# RoboKit.net
KiCad netlist of a schematic drawn in EAGLE
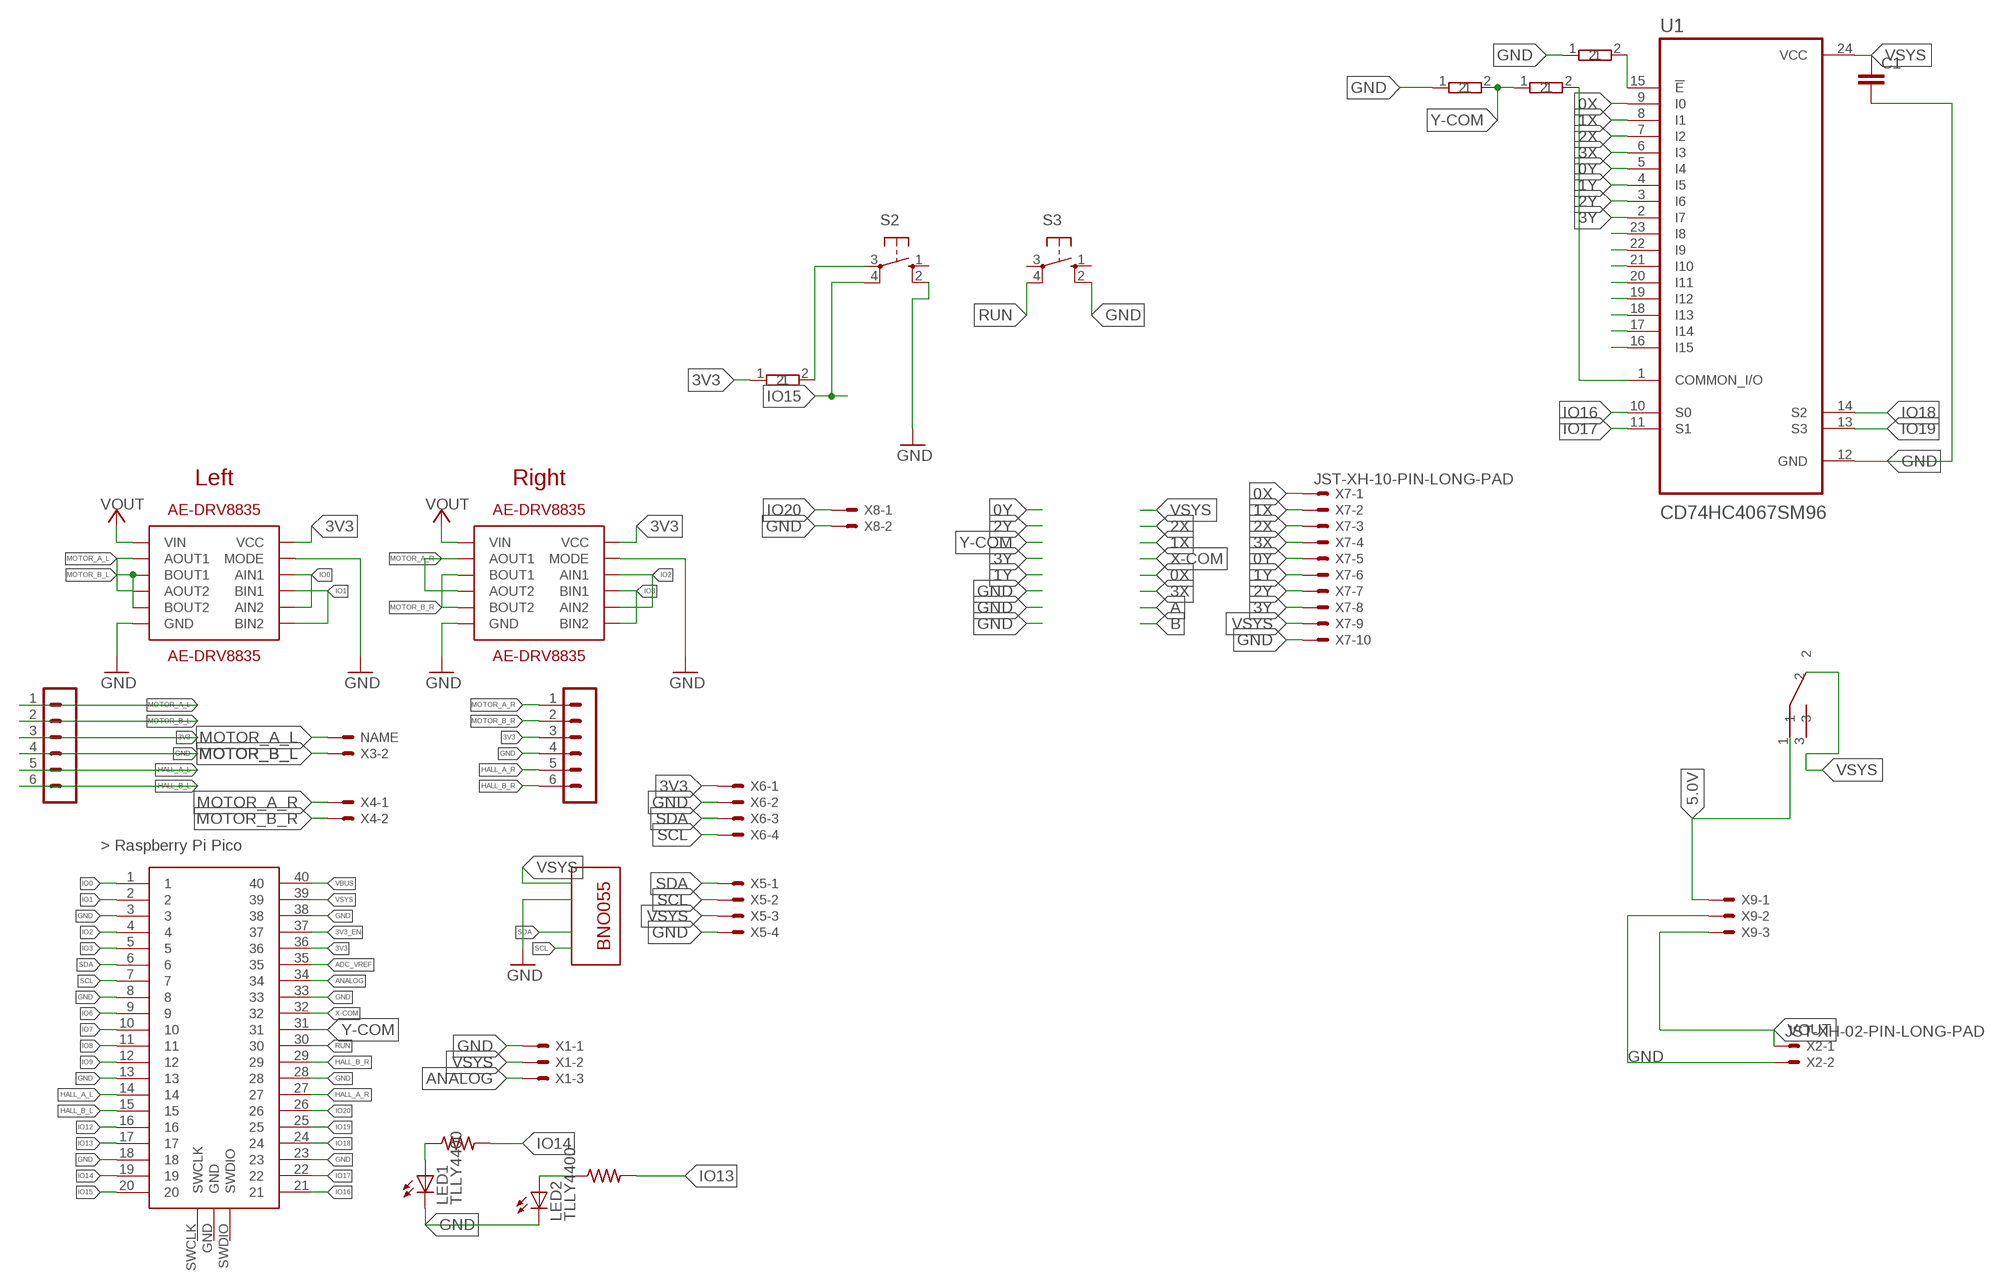
[diagram p0: schematic, sheet 1]

(export (version "E")
  (design (tool "Eeschema 10.0.6"))
  (components
    (comp (ref "C1")
      (value "C-EU025-024X044")
      (footprint "eagle-import:C025-024X044")
      (libsource (lib "eagle-import") (part "C-EU025-024X044"))
    )
    (comp (ref "CONNECTOR1")
      (value "RESISTER")
      (footprint "eagle-import:RESISTER_SOCKET")
      (libsource (lib "eagle-import") (part "RESISTER"))
    )
    (comp (ref "CONNECTOR4")
      (value "RESISTER")
      (footprint "eagle-import:RESISTER_SOCKET")
      (libsource (lib "eagle-import") (part "RESISTER"))
    )
    (comp (ref "CONNECTOR5")
      (value "RESISTER")
      (footprint "eagle-import:RESISTER_SOCKET")
      (libsource (lib "eagle-import") (part "RESISTER"))
    )
    (comp (ref "CONNECTOR6")
      (value "RESISTER")
      (footprint "eagle-import:RESISTER_SOCKET")
      (libsource (lib "eagle-import") (part "RESISTER"))
    )
    (comp (ref "LED1")
      (value "TLLY4400")
      (footprint "eagle-import:LED3MM")
      (fields (field (name "MF") "VISHAY SEMICONDUCTOR"))
      (libsource (lib "eagle-import") (part "TLLY4400"))
    )
    (comp (ref "LED2")
      (value "TLLY4400")
      (footprint "eagle-import:LED3MM")
      (fields (field (name "MF") "VISHAY SEMICONDUCTOR"))
      (libsource (lib "eagle-import") (part "TLLY4400"))
    )
    (comp (ref "P1")
      (value "B6B-PH-K")
      (footprint "eagle-import:B6B-PH-K")
      (libsource (lib "eagle-import") (part "B6B-PH-K"))
    )
    (comp (ref "P2")
      (value "B6B-PH-K")
      (footprint "eagle-import:B6B-PH-K")
      (libsource (lib "eagle-import") (part "B6B-PH-K"))
    )
    (comp (ref "R2")
      (value "R-US_R0603")
      (footprint "eagle-import:R0603")
      (libsource (lib "eagle-import") (part "R-US_R0603"))
    )
    (comp (ref "R3")
      (value "R-US_R0603")
      (footprint "eagle-import:R0603")
      (libsource (lib "eagle-import") (part "R-US_R0603"))
    )
    (comp (ref "S2")
      (value "40-XX")
      (footprint "eagle-import:B3F-40XX")
      (fields (field (name "MF") "OMRON COMPONENTS USA") (field (name "MPN") "B3F-4000"))
      (libsource (lib "eagle-import") (part "40-XX"))
    )
    (comp (ref "S3")
      (value "10-XX")
      (footprint "eagle-import:B3F-10XX")
      (fields (field (name "MPN") "B3F-1000"))
      (libsource (lib "eagle-import") (part "10-XX"))
    )
    (comp (ref "U$1")
      (value "RASPBERRY-PI-PICO_TH")
      (footprint "eagle-import:FT_RASPBERRY-PI-PICO_TH")
      (libsource (lib "eagle-import") (part "RASPBERRY-PI-PICO_TH"))
    )
    (comp (ref "U$2")
      (value "AE-DRV8835")
      (footprint "eagle-import:AE-DRV8835")
      (libsource (lib "eagle-import") (part "AE-DRV8835"))
    )
    (comp (ref "U$3")
      (value "AE-DRV8835")
      (footprint "eagle-import:AE-DRV8835")
      (libsource (lib "eagle-import") (part "AE-DRV8835"))
    )
    (comp (ref "U$4")
      (value "AE-BNO055-BO")
      (footprint "eagle-import:AE-BNO055-BO")
      (libsource (lib "eagle-import") (part "AE-BNO055-BO"))
    )
    (comp (ref "U$8") (value "SW") (footprint "eagle-import:SW") (libsource (lib "eagle-import") (part "SW")))
    (comp (ref "U1")
      (value "CD74HC4067SM96")
      (footprint "eagle-import:SOP65P780X200-24N")
      (fields (field (name "MF") "Texas Instruments"))
      (libsource (lib "eagle-import") (part "CD74HC4067SM96"))
    )
    (comp (ref "X1")
      (value "JST-XH-03-PIN-LONG-PAD")
      (footprint "eagle-import:JST-XH-03-PACKAGE-LONG-PAD")
      (libsource (lib "eagle-import") (part "JST-XH-03-PIN-LONG-PAD"))
    )
    (comp (ref "X2")
      (value "JST-XH-02-PIN-LONG-PAD")
      (footprint "eagle-import:JST-XH-02-PACKAGE-LONG-PAD")
      (libsource (lib "eagle-import") (part "JST-XH-02-PIN-LONG-PAD"))
    )
    (comp (ref "X3")
      (value "JST-XH-02-PIN-LONG-PAD")
      (footprint "eagle-import:JST-XH-02-PACKAGE-LONG-PAD")
      (libsource (lib "eagle-import") (part "JST-XH-02-PIN-LONG-PAD"))
    )
    (comp (ref "X4")
      (value "JST-XH-02-PIN-LONG-PAD")
      (footprint "eagle-import:JST-XH-02-PACKAGE-LONG-PAD")
      (libsource (lib "eagle-import") (part "JST-XH-02-PIN-LONG-PAD"))
    )
    (comp (ref "X5")
      (value "JST-XH-04-PIN-LONG-PAD")
      (footprint "eagle-import:JST-XH-04-PACKAGE-LONG-PAD")
      (libsource (lib "eagle-import") (part "JST-XH-04-PIN-LONG-PAD"))
    )
    (comp (ref "X6")
      (value "JST-XH-04-PIN-LONG-PAD")
      (footprint "eagle-import:JST-XH-04-PACKAGE-LONG-PAD")
      (libsource (lib "eagle-import") (part "JST-XH-04-PIN-LONG-PAD"))
    )
    (comp (ref "X7")
      (value "JST-XH-10-PIN-LONG-PAD")
      (footprint "eagle-import:JST-XH-10-PACKAGE-LONG-PAD")
      (libsource (lib "eagle-import") (part "JST-XH-10-PIN-LONG-PAD"))
    )
    (comp (ref "X8")
      (value "JST-XH-02-PIN-LONG-PAD")
      (footprint "eagle-import:JST-XH-02-PACKAGE-LONG-PAD")
      (libsource (lib "eagle-import") (part "JST-XH-02-PIN-LONG-PAD"))
    )
    (comp (ref "X9")
      (value "JST-XH-03-PIN-LONG-PAD")
      (footprint "eagle-import:JST-XH-03-PACKAGE-LONG-PAD")
      (libsource (lib "eagle-import") (part "JST-XH-03-PIN-LONG-PAD"))
    )
  )
  (nets
    (net (code "1") (name "0X") (class "Default")
      (node (ref "U1") (pin "9") (pinfunction "I0_9") (pintype "input"))
      (node (ref "X7") (pin "1") (pinfunction "S_1") (pintype "passive"))
    )
    (net (code "2") (name "0Y") (class "Default")
      (node (ref "U1") (pin "5") (pinfunction "I4_5") (pintype "input"))
      (node (ref "X7") (pin "5") (pinfunction "S_5") (pintype "passive"))
    )
    (net (code "3") (name "1X") (class "Default")
      (node (ref "U1") (pin "8") (pinfunction "I1_8") (pintype "input"))
      (node (ref "X7") (pin "2") (pinfunction "S_2") (pintype "passive"))
    )
    (net (code "4") (name "1Y") (class "Default")
      (node (ref "U1") (pin "4") (pinfunction "I5_4") (pintype "input"))
      (node (ref "X7") (pin "6") (pinfunction "S_6") (pintype "passive"))
    )
    (net (code "5") (name "2X") (class "Default")
      (node (ref "U1") (pin "7") (pinfunction "I2_7") (pintype "input"))
      (node (ref "X7") (pin "3") (pinfunction "S_3") (pintype "passive"))
    )
    (net (code "6") (name "2Y") (class "Default")
      (node (ref "U1") (pin "3") (pinfunction "I6_3") (pintype "input"))
      (node (ref "X7") (pin "7") (pinfunction "S_7") (pintype "passive"))
    )
    (net (code "7") (name "3V3") (class "Default")
      (node (ref "CONNECTOR1") (pin "1") (pinfunction "1_1") (pintype "bidirectional"))
      (node (ref "P1") (pin "3") (pinfunction "3_3") (pintype "passive"))
      (node (ref "P2") (pin "3") (pinfunction "3_3") (pintype "passive"))
      (node (ref "U$1") (pin "36") (pinfunction "36_36") (pintype "bidirectional"))
      (node (ref "U$2") (pin "VCC") (pinfunction "VCC_VCC") (pintype "input"))
      (node (ref "U$3") (pin "VCC") (pinfunction "VCC_VCC") (pintype "input"))
      (node (ref "X6") (pin "1") (pinfunction "S_1") (pintype "passive"))
    )
    (net (code "8") (name "3V3_EN") (class "Default")
      (node (ref "U$1") (pin "37") (pinfunction "37_37") (pintype "bidirectional"))
    )
    (net (code "9") (name "3X") (class "Default")
      (node (ref "U1") (pin "6") (pinfunction "I3_6") (pintype "input"))
      (node (ref "X7") (pin "4") (pinfunction "S_4") (pintype "passive"))
    )
    (net (code "10") (name "3Y") (class "Default")
      (node (ref "U1") (pin "2") (pinfunction "I7_2") (pintype "input"))
      (node (ref "X7") (pin "8") (pinfunction "S_8") (pintype "passive"))
    )
    (net (code "11") (name "5.0V") (class "Default")
      (node (ref "U$8") (pin "1") (pinfunction "1_1") (pintype "bidirectional"))
      (node (ref "X9") (pin "1") (pinfunction "S_1") (pintype "passive"))
    )
    (net (code "13") (name "ADC_VREF") (class "Default")
      (node (ref "U$1") (pin "35") (pinfunction "35_35") (pintype "bidirectional"))
    )
    (net (code "14") (name "ANALOG") (class "Default")
      (node (ref "U$1") (pin "34") (pinfunction "34_34") (pintype "bidirectional"))
      (node (ref "X1") (pin "3") (pinfunction "S_3") (pintype "passive"))
    )
    (net (code "16") (name "GND") (class "Default")
      (node (ref "C1") (pin "2") (pinfunction "2_2") (pintype "passive"))
      (node (ref "CONNECTOR5") (pin "1") (pinfunction "1_1") (pintype "bidirectional"))
      (node (ref "CONNECTOR6") (pin "1") (pinfunction "1_1") (pintype "bidirectional"))
      (node (ref "LED1") (pin "K") (pinfunction "C_K") (pintype "passive"))
      (node (ref "LED2") (pin "K") (pinfunction "C_K") (pintype "passive"))
      (node (ref "P1") (pin "4") (pinfunction "4_4") (pintype "passive"))
      (node (ref "P2") (pin "4") (pinfunction "4_4") (pintype "passive"))
      (node (ref "S2") (pin "2") (pinfunction "S1_2") (pintype "passive"))
      (node (ref "S3") (pin "2") (pinfunction "S1_2") (pintype "passive"))
      (node (ref "U$1") (pin "13") (pinfunction "13_13") (pintype "bidirectional"))
      (node (ref "U$1") (pin "18") (pinfunction "18_18") (pintype "bidirectional"))
      (node (ref "U$1") (pin "23") (pinfunction "23_23") (pintype "bidirectional"))
      (node (ref "U$1") (pin "28") (pinfunction "28_28") (pintype "bidirectional"))
      (node (ref "U$1") (pin "3") (pinfunction "3_3") (pintype "bidirectional"))
      (node (ref "U$1") (pin "33") (pinfunction "33_33") (pintype "bidirectional"))
      (node (ref "U$1") (pin "38") (pinfunction "38_38") (pintype "bidirectional"))
      (node (ref "U$1") (pin "8") (pinfunction "8_8") (pintype "bidirectional"))
      (node (ref "U$2") (pin "GND") (pinfunction "GND_GND") (pintype "input"))
      (node (ref "U$2") (pin "MODE") (pinfunction "MODE_MODE") (pintype "input"))
      (node (ref "U$3") (pin "GND") (pinfunction "GND_GND") (pintype "input"))
      (node (ref "U$3") (pin "MODE") (pinfunction "MODE_MODE") (pintype "input"))
      (node (ref "U$4") (pin "GND") (pinfunction "GND_GND") (pintype "bidirectional"))
      (node (ref "U1") (pin "12") (pinfunction "GND_12") (pintype "power_in"))
      (node (ref "X1") (pin "1") (pinfunction "S_1") (pintype "passive"))
      (node (ref "X2") (pin "2") (pinfunction "S_2") (pintype "passive"))
      (node (ref "X5") (pin "4") (pinfunction "S_4") (pintype "passive"))
      (node (ref "X6") (pin "2") (pinfunction "S_2") (pintype "passive"))
      (node (ref "X7") (pin "10") (pinfunction "S_10") (pintype "passive"))
      (node (ref "X8") (pin "2") (pinfunction "S_2") (pintype "passive"))
      (node (ref "X9") (pin "2") (pinfunction "S_2") (pintype "passive"))
    )
    (net (code "17") (name "HALL_A_L") (class "Default")
      (node (ref "P2") (pin "5") (pinfunction "5_5") (pintype "passive"))
      (node (ref "U$1") (pin "14") (pinfunction "14_14") (pintype "bidirectional"))
    )
    (net (code "18") (name "HALL_A_R") (class "Default")
      (node (ref "P1") (pin "5") (pinfunction "5_5") (pintype "passive"))
      (node (ref "U$1") (pin "27") (pinfunction "27_27") (pintype "bidirectional"))
    )
    (net (code "19") (name "HALL_B_L") (class "Default")
      (node (ref "P2") (pin "6") (pinfunction "6_6") (pintype "passive"))
      (node (ref "U$1") (pin "15") (pinfunction "15_15") (pintype "bidirectional"))
    )
    (net (code "20") (name "HALL_B_R") (class "Default")
      (node (ref "P1") (pin "6") (pinfunction "6_6") (pintype "passive"))
      (node (ref "U$1") (pin "29") (pinfunction "29_29") (pintype "bidirectional"))
    )
    (net (code "21") (name "IO0") (class "Default")
      (node (ref "U$1") (pin "1") (pinfunction "1_1") (pintype "bidirectional"))
      (node (ref "U$2") (pin "INA1") (pinfunction "AIN1_INA1") (pintype "input"))
      (node (ref "U$2") (pin "INA2") (pinfunction "AIN2_INA2") (pintype "input"))
    )
    (net (code "22") (name "IO1") (class "Default")
      (node (ref "U$1") (pin "2") (pinfunction "2_2") (pintype "bidirectional"))
      (node (ref "U$2") (pin "INB1") (pinfunction "BIN1_INB1") (pintype "input"))
      (node (ref "U$2") (pin "INB2") (pinfunction "BIN2_INB2") (pintype "input"))
    )
    (net (code "23") (name "IO2") (class "Default")
      (node (ref "U$1") (pin "4") (pinfunction "4_4") (pintype "bidirectional"))
      (node (ref "U$3") (pin "INA1") (pinfunction "AIN1_INA1") (pintype "input"))
      (node (ref "U$3") (pin "INA2") (pinfunction "AIN2_INA2") (pintype "input"))
    )
    (net (code "24") (name "IO3") (class "Default")
      (node (ref "U$1") (pin "5") (pinfunction "5_5") (pintype "bidirectional"))
      (node (ref "U$3") (pin "INB1") (pinfunction "BIN1_INB1") (pintype "input"))
      (node (ref "U$3") (pin "INB2") (pinfunction "BIN2_INB2") (pintype "input"))
    )
    (net (code "25") (name "IO6") (class "Default")
      (node (ref "U$1") (pin "9") (pinfunction "9_9") (pintype "bidirectional"))
    )
    (net (code "26") (name "IO7") (class "Default")
      (node (ref "U$1") (pin "10") (pinfunction "10_10") (pintype "bidirectional"))
    )
    (net (code "27") (name "IO8") (class "Default")
      (node (ref "U$1") (pin "11") (pinfunction "11_11") (pintype "bidirectional"))
    )
    (net (code "28") (name "IO9") (class "Default")
      (node (ref "U$1") (pin "12") (pinfunction "12_12") (pintype "bidirectional"))
    )
    (net (code "29") (name "IO12") (class "Default")
      (node (ref "U$1") (pin "16") (pinfunction "16_16") (pintype "bidirectional"))
    )
    (net (code "30") (name "IO13") (class "Default")
      (node (ref "R3") (pin "2") (pinfunction "2_2") (pintype "passive"))
      (node (ref "U$1") (pin "17") (pinfunction "17_17") (pintype "bidirectional"))
    )
    (net (code "31") (name "IO14") (class "Default")
      (node (ref "R2") (pin "2") (pinfunction "2_2") (pintype "passive"))
      (node (ref "U$1") (pin "19") (pinfunction "19_19") (pintype "bidirectional"))
    )
    (net (code "32") (name "IO15") (class "Default")
      (node (ref "S2") (pin "4") (pinfunction "P1_4") (pintype "passive"))
      (node (ref "U$1") (pin "20") (pinfunction "20_20") (pintype "bidirectional"))
    )
    (net (code "33") (name "IO16") (class "Default")
      (node (ref "U$1") (pin "21") (pinfunction "21_21") (pintype "bidirectional"))
      (node (ref "U1") (pin "10") (pinfunction "S0_10") (pintype "bidirectional"))
    )
    (net (code "34") (name "IO17") (class "Default")
      (node (ref "U$1") (pin "22") (pinfunction "22_22") (pintype "bidirectional"))
      (node (ref "U1") (pin "11") (pinfunction "S1_11") (pintype "bidirectional"))
    )
    (net (code "35") (name "IO18") (class "Default")
      (node (ref "U$1") (pin "24") (pinfunction "24_24") (pintype "bidirectional"))
      (node (ref "U1") (pin "14") (pinfunction "S2_14") (pintype "bidirectional"))
    )
    (net (code "36") (name "IO19") (class "Default")
      (node (ref "U$1") (pin "25") (pinfunction "25_25") (pintype "bidirectional"))
      (node (ref "U1") (pin "13") (pinfunction "S3_13") (pintype "bidirectional"))
    )
    (net (code "37") (name "IO20") (class "Default")
      (node (ref "U$1") (pin "26") (pinfunction "26_26") (pintype "bidirectional"))
      (node (ref "X8") (pin "1") (pinfunction "S_1") (pintype "passive"))
    )
    (net (code "38") (name "MOTOR_A_L") (class "Default")
      (node (ref "P2") (pin "1") (pinfunction "1_1") (pintype "passive"))
      (node (ref "U$2") (pin "AOUT1") (pinfunction "AOUT1_AOUT1") (pintype "input"))
      (node (ref "U$2") (pin "AOUT2") (pinfunction "AOUT2_AOUT2") (pintype "input"))
      (node (ref "X3") (pin "1") (pinfunction "S_1") (pintype "passive"))
    )
    (net (code "39") (name "MOTOR_A_R") (class "Default")
      (node (ref "P1") (pin "1") (pinfunction "1_1") (pintype "passive"))
      (node (ref "U$3") (pin "AOUT1") (pinfunction "AOUT1_AOUT1") (pintype "input"))
      (node (ref "U$3") (pin "AOUT2") (pinfunction "AOUT2_AOUT2") (pintype "input"))
      (node (ref "X4") (pin "1") (pinfunction "S_1") (pintype "passive"))
    )
    (net (code "40") (name "MOTOR_B_L") (class "Default")
      (node (ref "P2") (pin "2") (pinfunction "2_2") (pintype "passive"))
      (node (ref "U$2") (pin "BOUT1") (pinfunction "BOUT1_BOUT1") (pintype "input"))
      (node (ref "U$2") (pin "BOUT2") (pinfunction "BOUT2_BOUT2") (pintype "input"))
      (node (ref "X3") (pin "2") (pinfunction "S_2") (pintype "passive"))
    )
    (net (code "41") (name "MOTOR_B_R") (class "Default")
      (node (ref "P1") (pin "2") (pinfunction "2_2") (pintype "passive"))
      (node (ref "U$3") (pin "BOUT1") (pinfunction "BOUT1_BOUT1") (pintype "input"))
      (node (ref "U$3") (pin "BOUT2") (pinfunction "BOUT2_BOUT2") (pintype "input"))
      (node (ref "X4") (pin "2") (pinfunction "S_2") (pintype "passive"))
    )
    (net (code "42") (name "Net-(LED1-PadA)") (class "Default")
      (node (ref "LED1") (pin "A") (pinfunction "A_A") (pintype "passive"))
      (node (ref "R2") (pin "1") (pinfunction "1_1") (pintype "passive"))
    )
    (net (code "43") (name "Net-(LED2-PadA)") (class "Default")
      (node (ref "LED2") (pin "A") (pinfunction "A_A") (pintype "passive"))
      (node (ref "R3") (pin "1") (pinfunction "1_1") (pintype "passive"))
    )
    (net (code "44") (name "Net-(S2-P)") (class "Default")
      (node (ref "CONNECTOR1") (pin "2") (pinfunction "2_2") (pintype "bidirectional"))
      (node (ref "S2") (pin "3") (pinfunction "P_3") (pintype "passive"))
    )
    (net (code "45") (name "Net-(U1-COMMON_I{slash}O)") (class "Default")
      (node (ref "CONNECTOR4") (pin "2") (pinfunction "2_2") (pintype "bidirectional"))
      (node (ref "U1") (pin "1") (pinfunction "COMMON_I/O_1") (pintype "bidirectional"))
    )
    (net (code "46") (name "Net-(U1-~{E})") (class "Default")
      (node (ref "CONNECTOR6") (pin "2") (pinfunction "2_2") (pintype "bidirectional"))
      (node (ref "U1") (pin "15") (pinfunction "~{E}_15") (pintype "input"))
    )
    (net (code "47") (name "RUN") (class "Default")
      (node (ref "S3") (pin "4") (pinfunction "P1_4") (pintype "passive"))
      (node (ref "U$1") (pin "30") (pinfunction "30_30") (pintype "bidirectional"))
    )
    (net (code "48") (name "SCL") (class "Default")
      (node (ref "U$1") (pin "7") (pinfunction "7_7") (pintype "bidirectional"))
      (node (ref "U$4") (pin "SCL") (pinfunction "SCL_SCL") (pintype "bidirectional"))
      (node (ref "X5") (pin "2") (pinfunction "S_2") (pintype "passive"))
      (node (ref "X6") (pin "4") (pinfunction "S_4") (pintype "passive"))
    )
    (net (code "49") (name "SDA") (class "Default")
      (node (ref "U$1") (pin "6") (pinfunction "6_6") (pintype "bidirectional"))
      (node (ref "U$4") (pin "SDA") (pinfunction "SDA_SDA") (pintype "bidirectional"))
      (node (ref "X5") (pin "1") (pinfunction "S_1") (pintype "passive"))
      (node (ref "X6") (pin "3") (pinfunction "S_3") (pintype "passive"))
    )
    (net (code "50") (name "VBUS") (class "Default")
      (node (ref "U$1") (pin "40") (pinfunction "40_40") (pintype "bidirectional"))
    )
    (net (code "51") (name "VOUT") (class "Default")
      (node (ref "U$2") (pin "VIN") (pinfunction "VIN_VIN") (pintype "input"))
      (node (ref "U$3") (pin "VIN") (pinfunction "VIN_VIN") (pintype "input"))
      (node (ref "X2") (pin "1") (pinfunction "S_1") (pintype "passive"))
      (node (ref "X9") (pin "3") (pinfunction "S_3") (pintype "passive"))
    )
    (net (code "52") (name "VSYS") (class "Default")
      (node (ref "C1") (pin "1") (pinfunction "1_1") (pintype "passive"))
      (node (ref "U$1") (pin "39") (pinfunction "39_39") (pintype "bidirectional"))
      (node (ref "U$4") (pin "VIN") (pinfunction "VIN_VIN") (pintype "bidirectional"))
      (node (ref "U$8") (pin "2") (pinfunction "2_2") (pintype "bidirectional"))
      (node (ref "U1") (pin "24") (pinfunction "VCC_24") (pintype "power_in"))
      (node (ref "X1") (pin "2") (pinfunction "S_2") (pintype "passive"))
      (node (ref "X5") (pin "3") (pinfunction "S_3") (pintype "passive"))
      (node (ref "X7") (pin "9") (pinfunction "S_9") (pintype "passive"))
    )
    (net (code "53") (name "X-COM") (class "Default")
      (node (ref "U$1") (pin "32") (pinfunction "32_32") (pintype "bidirectional"))
    )
    (net (code "54") (name "Y-COM") (class "Default")
      (node (ref "CONNECTOR4") (pin "1") (pinfunction "1_1") (pintype "bidirectional"))
      (node (ref "CONNECTOR5") (pin "2") (pinfunction "2_2") (pintype "bidirectional"))
      (node (ref "U$1") (pin "31") (pinfunction "31_31") (pintype "bidirectional"))
    )
    (net (code "55") (name "unconnected-(S2-S-Pad1)") (class "Default")
      (node (ref "S2") (pin "1") (pinfunction "S_1") (pintype "passive"))
    )
    (net (code "56") (name "unconnected-(S3-P-Pad3)") (class "Default")
      (node (ref "S3") (pin "3") (pinfunction "P_3") (pintype "passive"))
    )
    (net (code "57") (name "unconnected-(S3-S-Pad1)") (class "Default")
      (node (ref "S3") (pin "1") (pinfunction "S_1") (pintype "passive"))
    )
    (net (code "58") (name "unconnected-(U$1-PadGND)") (class "Default")
      (node (ref "U$1") (pin "GND") (pinfunction "GND_GND") (pintype "bidirectional"))
    )
    (net (code "59") (name "unconnected-(U$1-PadSWCLK)") (class "Default")
      (node (ref "U$1") (pin "SWCLK") (pinfunction "SWCLK_SWCLK") (pintype "bidirectional"))
    )
    (net (code "60") (name "unconnected-(U$1-PadSWDIO)") (class "Default")
      (node (ref "U$1") (pin "SWDIO") (pinfunction "SWDIO_SWDIO") (pintype "bidirectional"))
    )
    (net (code "61") (name "unconnected-(U$8-Pad3)") (class "Default")
      (node (ref "U$8") (pin "3") (pinfunction "3_3") (pintype "bidirectional"))
    )
    (net (code "62") (name "unconnected-(U1-I8-Pad23)") (class "Default")
      (node (ref "U1") (pin "23") (pinfunction "I8_23") (pintype "input"))
    )
    (net (code "63") (name "unconnected-(U1-I9-Pad22)") (class "Default")
      (node (ref "U1") (pin "22") (pinfunction "I9_22") (pintype "input"))
    )
    (net (code "64") (name "unconnected-(U1-I10-Pad21)") (class "Default")
      (node (ref "U1") (pin "21") (pinfunction "I10_21") (pintype "input"))
    )
    (net (code "65") (name "unconnected-(U1-I11-Pad20)") (class "Default")
      (node (ref "U1") (pin "20") (pinfunction "I11_20") (pintype "input"))
    )
    (net (code "66") (name "unconnected-(U1-I12-Pad19)") (class "Default")
      (node (ref "U1") (pin "19") (pinfunction "I12_19") (pintype "input"))
    )
    (net (code "67") (name "unconnected-(U1-I13-Pad18)") (class "Default")
      (node (ref "U1") (pin "18") (pinfunction "I13_18") (pintype "input"))
    )
    (net (code "68") (name "unconnected-(U1-I14-Pad17)") (class "Default")
      (node (ref "U1") (pin "17") (pinfunction "I14_17") (pintype "input"))
    )
    (net (code "69") (name "unconnected-(U1-I15-Pad16)") (class "Default")
      (node (ref "U1") (pin "16") (pinfunction "I15_16") (pintype "input"))
    )
  )
)
